# Current_Voltage_Sensor.net
KiCad netlist of a schematic drawn in Altium Designer
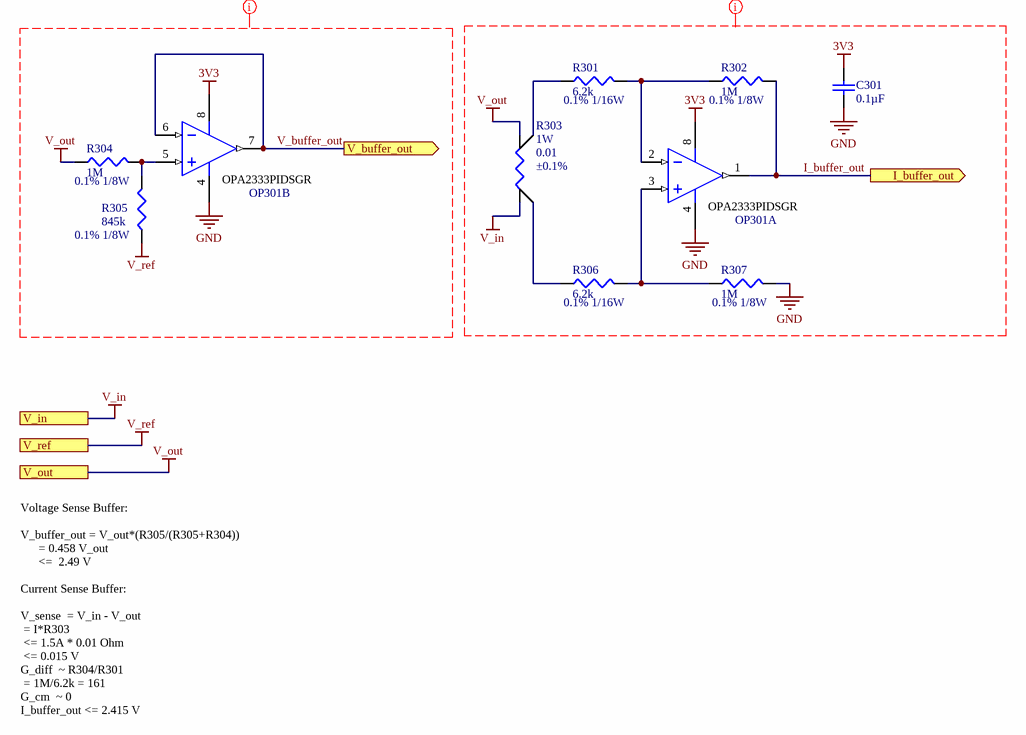
[diagram p0: Current_Voltage_Sensor.SchDoc]

(export (version "E")
  (design (tool "Eeschema 10.0.6"))
  (components
    (comp (ref "C301")
      (value "0.1µF")
      (footprint "TDK-CGA2B")
      (description "CAP CER 0.1UF 35V X7R 0402")
      (fields
        (field (name "PART NUMBER") "PC-TDK-02255")
        (field (name "MANUFACTURER PART NUMBER") "CGA2B3X7R1V104K050BB")
        (field (name "PUBLISHER") "AlbertaSat")
      )
      (libsource (lib "Database") (part "Cap"))
    )
    (comp (ref "OP301")
      (value "OPA2333")
      (footprint "TI-DSG0008A")
      (description "CMOS Amplifier 2 Circuit Rail-to-Rail 8-WSON (2x2)")
      (fields (field (name "PART NUMBER") "73") (field (name "MANUFACTURER PART NUMBER") "OPA2333PIDSGR"))
      (libsource (lib "Database") (part "OPA2333"))
    )
    (comp (ref "R301")
      (value "0.1% 1/16W")
      (footprint "PANA-ERA2A")
      (description "RES SMD 6.2K OHM 0.1% 1/16W 0402")
      (fields
        (field (name "ALTIUM_VALUE") "6.2k")
        (field (name "PART NUMBER") "16853")
        (field (name "MANUFACTURER PART NUMBER") "ERA-2APB622X")
        (field (name "PUBLISHER") "Altium Limited")
      )
      (libsource (lib "Database") (part "Res3"))
    )
    (comp (ref "R302")
      (value "0.1% 1/8W")
      (footprint "PANA-ERA6A")
      (description "RES SMD 1M OHM 0.1% 1/8W 0805")
      (fields
        (field (name "ALTIUM_VALUE") "1M")
        (field (name "PART NUMBER") "19706")
        (field (name "MANUFACTURER PART NUMBER") "ERA-6AEB105V")
        (field (name "PUBLISHER") "Altium Limited")
      )
      (libsource (lib "Database") (part "Res3"))
    )
    (comp (ref "R303")
      (value "0.01")
      (footprint "VSH-2512R4C")
      (description "RES SMD 0.01 OHM 0.1% 1W 2512")
      (fields
        (field (name "POWER - RATED") "1W")
        (field (name "TOLERANCE") "±0.1%")
        (field (name "PART NUMBER") "PR-VSH-00237")
        (field (name "MANUFACTURER PART NUMBER") "Y14870R01000B9W")
        (field (name "PUBLISHER") "AlbertaSat")
      )
      (libsource (lib "Database") (part "Res Sense"))
    )
    (comp (ref "R304")
      (value "0.1% 1/8W")
      (footprint "PANA-ERA6A")
      (description "RES SMD 1M OHM 0.1% 1/8W 0805")
      (fields
        (field (name "ALTIUM_VALUE") "1M")
        (field (name "PART NUMBER") "19706")
        (field (name "MANUFACTURER PART NUMBER") "ERA-6AEB105V")
        (field (name "PUBLISHER") "Altium Limited")
      )
      (libsource (lib "Database") (part "Res3"))
    )
    (comp (ref "R305")
      (value "0.1% 1/8W")
      (footprint "PANA-ERA6A")
      (description "RES SMD 845K OHM 0.1% 1/8W 0805")
      (fields
        (field (name "ALTIUM_VALUE") "845k")
        (field (name "PART NUMBER") "19643")
        (field (name "MANUFACTURER PART NUMBER") "ERA-6AEB8453V")
        (field (name "PUBLISHER") "Altium Limited")
      )
      (libsource (lib "Database") (part "Res3"))
    )
    (comp (ref "R306")
      (value "0.1% 1/16W")
      (footprint "PANA-ERA2A")
      (description "RES SMD 6.2K OHM 0.1% 1/16W 0402")
      (fields
        (field (name "ALTIUM_VALUE") "6.2k")
        (field (name "PART NUMBER") "16853")
        (field (name "MANUFACTURER PART NUMBER") "ERA-2APB622X")
        (field (name "PUBLISHER") "Altium Limited")
      )
      (libsource (lib "Database") (part "Res3"))
    )
    (comp (ref "R307")
      (value "0.1% 1/8W")
      (footprint "PANA-ERA6A")
      (description "RES SMD 1M OHM 0.1% 1/8W 0805")
      (fields
        (field (name "ALTIUM_VALUE") "1M")
        (field (name "PART NUMBER") "19706")
        (field (name "MANUFACTURER PART NUMBER") "ERA-6AEB105V")
        (field (name "PUBLISHER") "Altium Limited")
      )
      (libsource (lib "Database") (part "Res3"))
    )
  )
  (nets
    (net (code "1") (name "/I_buffer_out") (class "Default")
      (node (ref "OP301") (pin "1") (pinfunction "OUT_1") (pintype "output"))
      (node (ref "R302") (pin "2") (pinfunction "2_2") (pintype "passive"))
    )
    (net (code "2") (name "/V_buffer_out") (class "Default")
      (node (ref "OP301") (pin "6") (pinfunction "IN-_6") (pintype "input"))
      (node (ref "OP301") (pin "7") (pinfunction "OUT_7") (pintype "output"))
    )
    (net (code "3") (name "3V3") (class "Default")
      (node (ref "C301") (pin "2") (pinfunction "2_2") (pintype "passive"))
      (node (ref "OP301") (pin "8") (pinfunction "V+_8") (pintype "power_in"))
    )
    (net (code "4") (name "GND") (class "Default")
      (node (ref "C301") (pin "1") (pinfunction "1_1") (pintype "passive"))
      (node (ref "OP301") (pin "4") (pinfunction "V-_4") (pintype "power_in"))
      (node (ref "R307") (pin "2") (pinfunction "2_2") (pintype "passive"))
    )
    (net (code "5") (name "Net-(OP301A-IN+)") (class "Default")
      (node (ref "OP301") (pin "3") (pinfunction "IN+_3") (pintype "input"))
      (node (ref "R306") (pin "2") (pinfunction "2_2") (pintype "passive"))
      (node (ref "R307") (pin "1") (pinfunction "1_1") (pintype "passive"))
    )
    (net (code "6") (name "Net-(OP301A-IN-)") (class "Default")
      (node (ref "OP301") (pin "2") (pinfunction "IN-_2") (pintype "input"))
      (node (ref "R301") (pin "2") (pinfunction "2_2") (pintype "passive"))
      (node (ref "R302") (pin "1") (pinfunction "1_1") (pintype "passive"))
    )
    (net (code "7") (name "Net-(OP301B-IN+)") (class "Default")
      (node (ref "OP301") (pin "5") (pinfunction "IN+_5") (pintype "input"))
      (node (ref "R304") (pin "2") (pinfunction "2_2") (pintype "passive"))
      (node (ref "R305") (pin "2") (pinfunction "2_2") (pintype "passive"))
    )
    (net (code "8") (name "Net-(R303-S1)") (class "Default")
      (node (ref "R303") (pin "4") (pinfunction "S1_4") (pintype "passive"))
      (node (ref "R306") (pin "1") (pinfunction "1_1") (pintype "passive"))
    )
    (net (code "9") (name "Net-(R303-S2)") (class "Default")
      (node (ref "R301") (pin "1") (pinfunction "1_1") (pintype "passive"))
      (node (ref "R303") (pin "3") (pinfunction "S2_3") (pintype "passive"))
    )
    (net (code "10") (name "V_in") (class "Default")
      (node (ref "R303") (pin "1") (pinfunction "I1_1") (pintype "passive"))
    )
    (net (code "11") (name "V_out") (class "Default")
      (node (ref "R303") (pin "2") (pinfunction "I2_2") (pintype "passive"))
      (node (ref "R304") (pin "1") (pinfunction "1_1") (pintype "passive"))
    )
    (net (code "12") (name "V_ref") (class "Default")
      (node (ref "R305") (pin "1") (pinfunction "1_1") (pintype "passive"))
    )
  )
)
